# exercise1_1.net
KiCad netlist of a schematic drawn in Altium Designer
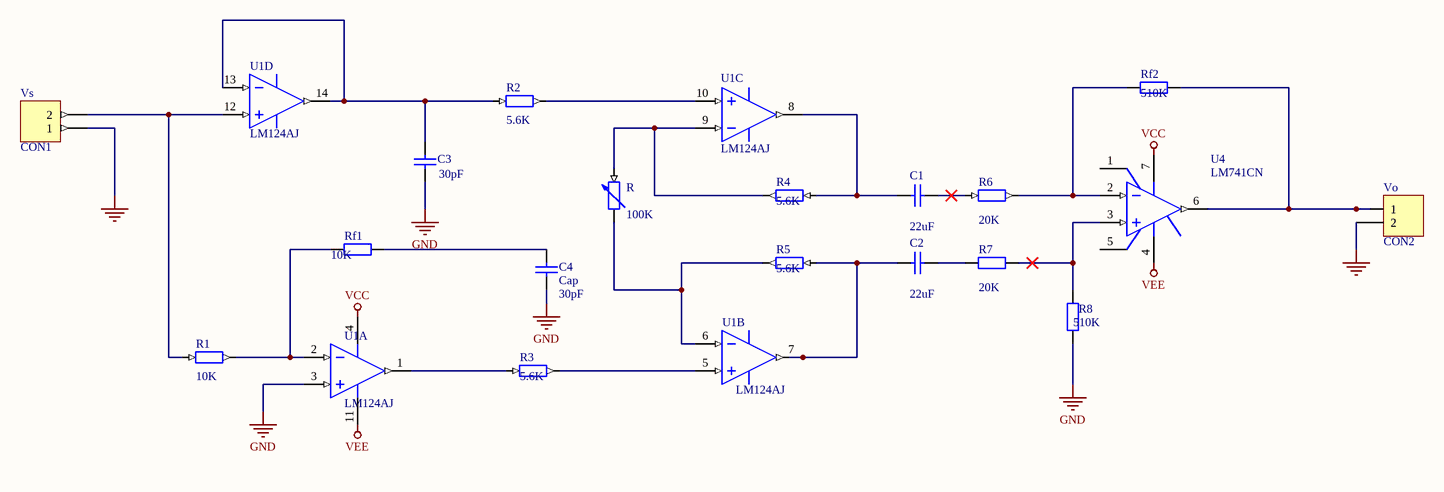
[diagram p0: exercise1_1.SchDoc]

(export (version "E")
  (design (tool "Eeschema 10.0.6"))
  (components
    (comp (ref "C1")
      (value "22uF")
      (footprint "RAD-0.3")
      (description "Capacitor")
      (fields (field (name "Comment") "Cap") (field (name "PUBLISHER") "Altium Limited"))
      (libsource (lib "Miscellaneous Devices") (part "Cap"))
    )
    (comp (ref "C2")
      (value "22uF")
      (footprint "RAD-0.3")
      (description "Capacitor")
      (fields (field (name "Comment") "Cap") (field (name "PUBLISHER") "Altium Limited"))
      (libsource (lib "Miscellaneous Devices") (part "Cap"))
    )
    (comp (ref "C3")
      (value "30pF")
      (footprint "RAD-0.3")
      (description "Capacitor")
      (fields (field (name "PUBLISHER") "Altium Limited"))
      (libsource (lib "Miscellaneous Devices") (part "Cap"))
    )
    (comp (ref "C4")
      (value "Cap")
      (footprint "RAD-0.3")
      (description "Capacitor")
      (fields (field (name "ALTIUM_VALUE") "30pF") (field (name "PUBLISHER") "Altium Limited"))
      (libsource (lib "Miscellaneous Devices") (part "Cap"))
    )
    (comp (ref "R")
      (value "100K")
      (footprint "AXIAL-0.6")
      (description "Variable Resistor")
      (fields (field (name "Comment") "Res Adj2") (field (name "PUBLISHER") "Altium Limited"))
      (libsource (lib "Miscellaneous Devices") (part "Res Adj2"))
    )
    (comp (ref "R1")
      (value "10K")
      (footprint "AXIAL-0.4")
      (description "Resistor")
      (fields (field (name "Comment") "Res2") (field (name "PUBLISHER") "Altium Limited"))
      (libsource (lib "Miscellaneous Devices") (part "Res2"))
    )
    (comp (ref "R2")
      (value "5.6K")
      (footprint "AXIAL-0.4")
      (description "Resistor")
      (fields (field (name "Comment") "Res2") (field (name "PUBLISHER") "Altium Limited"))
      (libsource (lib "Miscellaneous Devices") (part "Res2"))
    )
    (comp (ref "R3")
      (value "5.6K")
      (footprint "AXIAL-0.4")
      (description "Resistor")
      (fields (field (name "Comment") "Res2") (field (name "PUBLISHER") "Altium Limited"))
      (libsource (lib "Miscellaneous Devices") (part "Res2"))
    )
    (comp (ref "R4")
      (value "5.6K")
      (footprint "AXIAL-0.4")
      (description "Resistor")
      (fields (field (name "Comment") "Res2") (field (name "PUBLISHER") "Altium Limited"))
      (libsource (lib "Miscellaneous Devices") (part "Res2"))
    )
    (comp (ref "R5")
      (value "5.6K")
      (footprint "AXIAL-0.4")
      (description "Resistor")
      (fields (field (name "Comment") "Res2") (field (name "PUBLISHER") "Altium Limited"))
      (libsource (lib "Miscellaneous Devices") (part "Res2"))
    )
    (comp (ref "R6")
      (value "20K")
      (footprint "AXIAL-0.4")
      (description "Resistor")
      (fields (field (name "Comment") "Res2") (field (name "PUBLISHER") "Altium Limited"))
      (libsource (lib "Miscellaneous Devices") (part "Res2"))
    )
    (comp (ref "R7")
      (value "20K")
      (footprint "AXIAL-0.4")
      (description "Resistor")
      (fields (field (name "Comment") "Res2") (field (name "PUBLISHER") "Altium Limited"))
      (libsource (lib "Miscellaneous Devices") (part "Res2"))
    )
    (comp (ref "R8")
      (value "510K")
      (footprint "AXIAL-0.4")
      (description "Resistor")
      (fields (field (name "Comment") "Res2") (field (name "PUBLISHER") "Altium Limited"))
      (libsource (lib "") (part "Res2_1"))
    )
    (comp (ref "Rf1")
      (value "10K")
      (footprint "AXIAL-0.4")
      (description "Resistor")
      (fields (field (name "Comment") "Res2") (field (name "PUBLISHER") "Altium Limited"))
      (libsource (lib "Miscellaneous Devices") (part "Res2"))
    )
    (comp (ref "Rf2")
      (value "510K")
      (footprint "AXIAL-0.4")
      (description "Resistor")
      (fields (field (name "Comment") "Res2") (field (name "PUBLISHER") "Altium Limited"))
      (libsource (lib "Miscellaneous Devices") (part "Res2"))
    )
    (comp (ref "U1")
      (value "LM124AJ")
      (footprint "J14A")
      (description "Low Power Quad Operational Amplifier, 14-pin CerDIP")
      (fields
        (field (name "MANUFACTURER") "National Semiconductor")
        (field (name "PUBLISHER") "Altium Limited")
      )
      (libsource (lib "NSC Amplifier") (part "LM124AJ"))
    )
    (comp (ref "U4")
      (value "LM741CN")
      (footprint "N08E")
      (description "Operational Amplifier, 8-pin MDIP")
      (fields
        (field (name "MANUFACTURER") "National Semiconductor")
        (field (name "PUBLISHER") "Altium Limited")
      )
      (libsource (lib "NSC Amplifier") (part "LM741CN"))
    )
    (comp (ref "Vo")
      (value "CON2")
      (footprint "HDR1X2")
      (description "Header, 2-Pin")
      (fields (field (name "PUBLISHER") "Altium Limited"))
      (libsource (lib "Miscellaneous Connectors") (part "Header 2"))
    )
    (comp (ref "Vs")
      (value "CON1")
      (footprint "HDR1X2")
      (description "Header, 2-Pin")
      (fields (field (name "PUBLISHER") "Altium Limited"))
      (libsource (lib "") (part "Header 2_1"))
    )
  )
  (nets
    (net (code "1") (name "GND") (class "Default")
      (node (ref "C3") (pin "1") (pinfunction "1_1") (pintype "passive"))
      (node (ref "C4") (pin "1") (pinfunction "1_1") (pintype "passive"))
      (node (ref "R8") (pin "1") (pinfunction "1_1") (pintype "passive"))
      (node (ref "U1") (pin "3") (pinfunction "IN1+_3") (pintype "input"))
      (node (ref "Vo") (pin "2") (pinfunction "2_2") (pintype "passive"))
      (node (ref "Vs") (pin "1") (pinfunction "1_1") (pintype "output"))
    )
    (net (code "2") (name "Net-(C1-Pad2)") (class "Default")
      (node (ref "C1") (pin "2") (pinfunction "2_2") (pintype "passive"))
      (node (ref "R6") (pin "1") (pinfunction "1_1") (pintype "input"))
    )
    (net (code "3") (name "Net-(C2-Pad2)") (class "Default")
      (node (ref "C2") (pin "2") (pinfunction "2_2") (pintype "passive"))
      (node (ref "R7") (pin "1") (pinfunction "1_1") (pintype "input"))
    )
    (net (code "4") (name "Net-(C4-Pad2)") (class "Default")
      (node (ref "C4") (pin "2") (pinfunction "2_2") (pintype "passive"))
      (node (ref "Rf1") (pin "2") (pinfunction "2_2") (pintype "output"))
    )
    (net (code "5") (name "Net-(U1A-IN1-)") (class "Default")
      (node (ref "R1") (pin "2") (pinfunction "2_2") (pintype "output"))
      (node (ref "Rf1") (pin "1") (pinfunction "1_1") (pintype "input"))
      (node (ref "U1") (pin "2") (pinfunction "IN1-_2") (pintype "input"))
    )
    (net (code "6") (name "Net-(U1A-OUT1)") (class "Default")
      (node (ref "R3") (pin "1") (pinfunction "1_1") (pintype "input"))
      (node (ref "U1") (pin "1") (pinfunction "OUT1_1") (pintype "output"))
    )
    (net (code "7") (name "Net-(U1B-IN2+)") (class "Default")
      (node (ref "R3") (pin "2") (pinfunction "2_2") (pintype "output"))
      (node (ref "U1") (pin "5") (pinfunction "IN2+_5") (pintype "input"))
    )
    (net (code "8") (name "Net-(U1B-IN2-)") (class "Default")
      (node (ref "R") (pin "1") (pinfunction "1_1") (pintype "passive"))
      (node (ref "R5") (pin "1") (pinfunction "1_1") (pintype "input"))
      (node (ref "U1") (pin "6") (pinfunction "IN2-_6") (pintype "input"))
    )
    (net (code "9") (name "Net-(U1B-OUT2)") (class "Default")
      (node (ref "C2") (pin "1") (pinfunction "1_1") (pintype "passive"))
      (node (ref "R5") (pin "2") (pinfunction "2_2") (pintype "output"))
      (node (ref "U1") (pin "7") (pinfunction "OUT2_7") (pintype "output"))
    )
    (net (code "10") (name "Net-(U1C-IN3+)") (class "Default")
      (node (ref "R2") (pin "2") (pinfunction "2_2") (pintype "output"))
      (node (ref "U1") (pin "10") (pinfunction "IN3+_10") (pintype "input"))
    )
    (net (code "11") (name "Net-(U1C-IN3-)") (class "Default")
      (node (ref "R") (pin "2") (pinfunction "2_2") (pintype "input"))
      (node (ref "R4") (pin "1") (pinfunction "1_1") (pintype "input"))
      (node (ref "U1") (pin "9") (pinfunction "IN3-_9") (pintype "input"))
    )
    (net (code "12") (name "Net-(U1C-OUT3)") (class "Default")
      (node (ref "C1") (pin "1") (pinfunction "1_1") (pintype "passive"))
      (node (ref "R4") (pin "2") (pinfunction "2_2") (pintype "output"))
      (node (ref "U1") (pin "8") (pinfunction "OUT3_8") (pintype "output"))
    )
    (net (code "13") (name "Net-(U1D-IN4+)") (class "Default")
      (node (ref "R1") (pin "1") (pinfunction "1_1") (pintype "input"))
      (node (ref "U1") (pin "12") (pinfunction "IN4+_12") (pintype "input"))
      (node (ref "Vs") (pin "2") (pinfunction "2_2") (pintype "output"))
    )
    (net (code "14") (name "Net-(U1D-IN4-)") (class "Default")
      (node (ref "C3") (pin "2") (pinfunction "2_2") (pintype "passive"))
      (node (ref "R2") (pin "1") (pinfunction "1_1") (pintype "input"))
      (node (ref "U1") (pin "13") (pinfunction "IN4-_13") (pintype "input"))
      (node (ref "U1") (pin "14") (pinfunction "OUT4_14") (pintype "output"))
    )
    (net (code "15") (name "Net-(U4-IN+)") (class "Default")
      (node (ref "R7") (pin "2") (pinfunction "2_2") (pintype "output"))
      (node (ref "R8") (pin "2") (pinfunction "2_2") (pintype "passive"))
      (node (ref "U4") (pin "3") (pinfunction "IN+_3") (pintype "input"))
    )
    (net (code "16") (name "Net-(U4-IN-)") (class "Default")
      (node (ref "R6") (pin "2") (pinfunction "2_2") (pintype "output"))
      (node (ref "Rf2") (pin "1") (pinfunction "1_1") (pintype "input"))
      (node (ref "U4") (pin "2") (pinfunction "IN-_2") (pintype "input"))
    )
    (net (code "17") (name "Net-(U4-OUT)") (class "Default")
      (node (ref "Rf2") (pin "2") (pinfunction "2_2") (pintype "output"))
      (node (ref "U4") (pin "6") (pinfunction "OUT_6") (pintype "output"))
      (node (ref "Vo") (pin "1") (pinfunction "1_1") (pintype "passive"))
    )
    (net (code "18") (name "VCC") (class "Default")
      (node (ref "U1") (pin "4") (pinfunction "V+1_4") (pintype "power_in"))
      (node (ref "U4") (pin "7") (pinfunction "V+_7") (pintype "power_in"))
    )
    (net (code "19") (name "VEE") (class "Default")
      (node (ref "U1") (pin "11") (pinfunction "GND1_11") (pintype "power_in"))
      (node (ref "U4") (pin "4") (pinfunction "V-_4") (pintype "power_in"))
    )
    (net (code "20") (name "unconnected-(U1B-GND1-Pad11)") (class "Default")
      (node (ref "U1") (pin "11") (pinfunction "GND1_11") (pintype "power_in"))
    )
    (net (code "21") (name "unconnected-(U1B-V+1-Pad4)") (class "Default")
      (node (ref "U1") (pin "4") (pinfunction "V+1_4") (pintype "power_in"))
    )
    (net (code "22") (name "unconnected-(U1C-GND1-Pad11)") (class "Default")
      (node (ref "U1") (pin "11") (pinfunction "GND1_11") (pintype "power_in"))
    )
    (net (code "23") (name "unconnected-(U1C-V+1-Pad4)") (class "Default")
      (node (ref "U1") (pin "4") (pinfunction "V+1_4") (pintype "power_in"))
    )
    (net (code "24") (name "unconnected-(U1D-GND1-Pad11)") (class "Default")
      (node (ref "U1") (pin "11") (pinfunction "GND1_11") (pintype "power_in"))
    )
    (net (code "25") (name "unconnected-(U1D-V+1-Pad4)") (class "Default")
      (node (ref "U1") (pin "4") (pinfunction "V+1_4") (pintype "power_in"))
    )
    (net (code "26") (name "unconnected-(U4-NC-Pad8)") (class "Default")
      (node (ref "U4") (pin "8") (pinfunction "NC_8") (pintype "passive"))
    )
    (net (code "27") (name "unconnected-(U4-OFS_NULL-Pad1)") (class "Default")
      (node (ref "U4") (pin "1") (pinfunction "OFS_NULL_1") (pintype "passive"))
    )
    (net (code "28") (name "unconnected-(U4-OFS_NULL-Pad5)") (class "Default")
      (node (ref "U4") (pin "5") (pinfunction "OFS_NULL_5") (pintype "passive"))
    )
  )
)
